# motoko_5_0.net
KiCad netlist of a schematic drawn in EAGLE
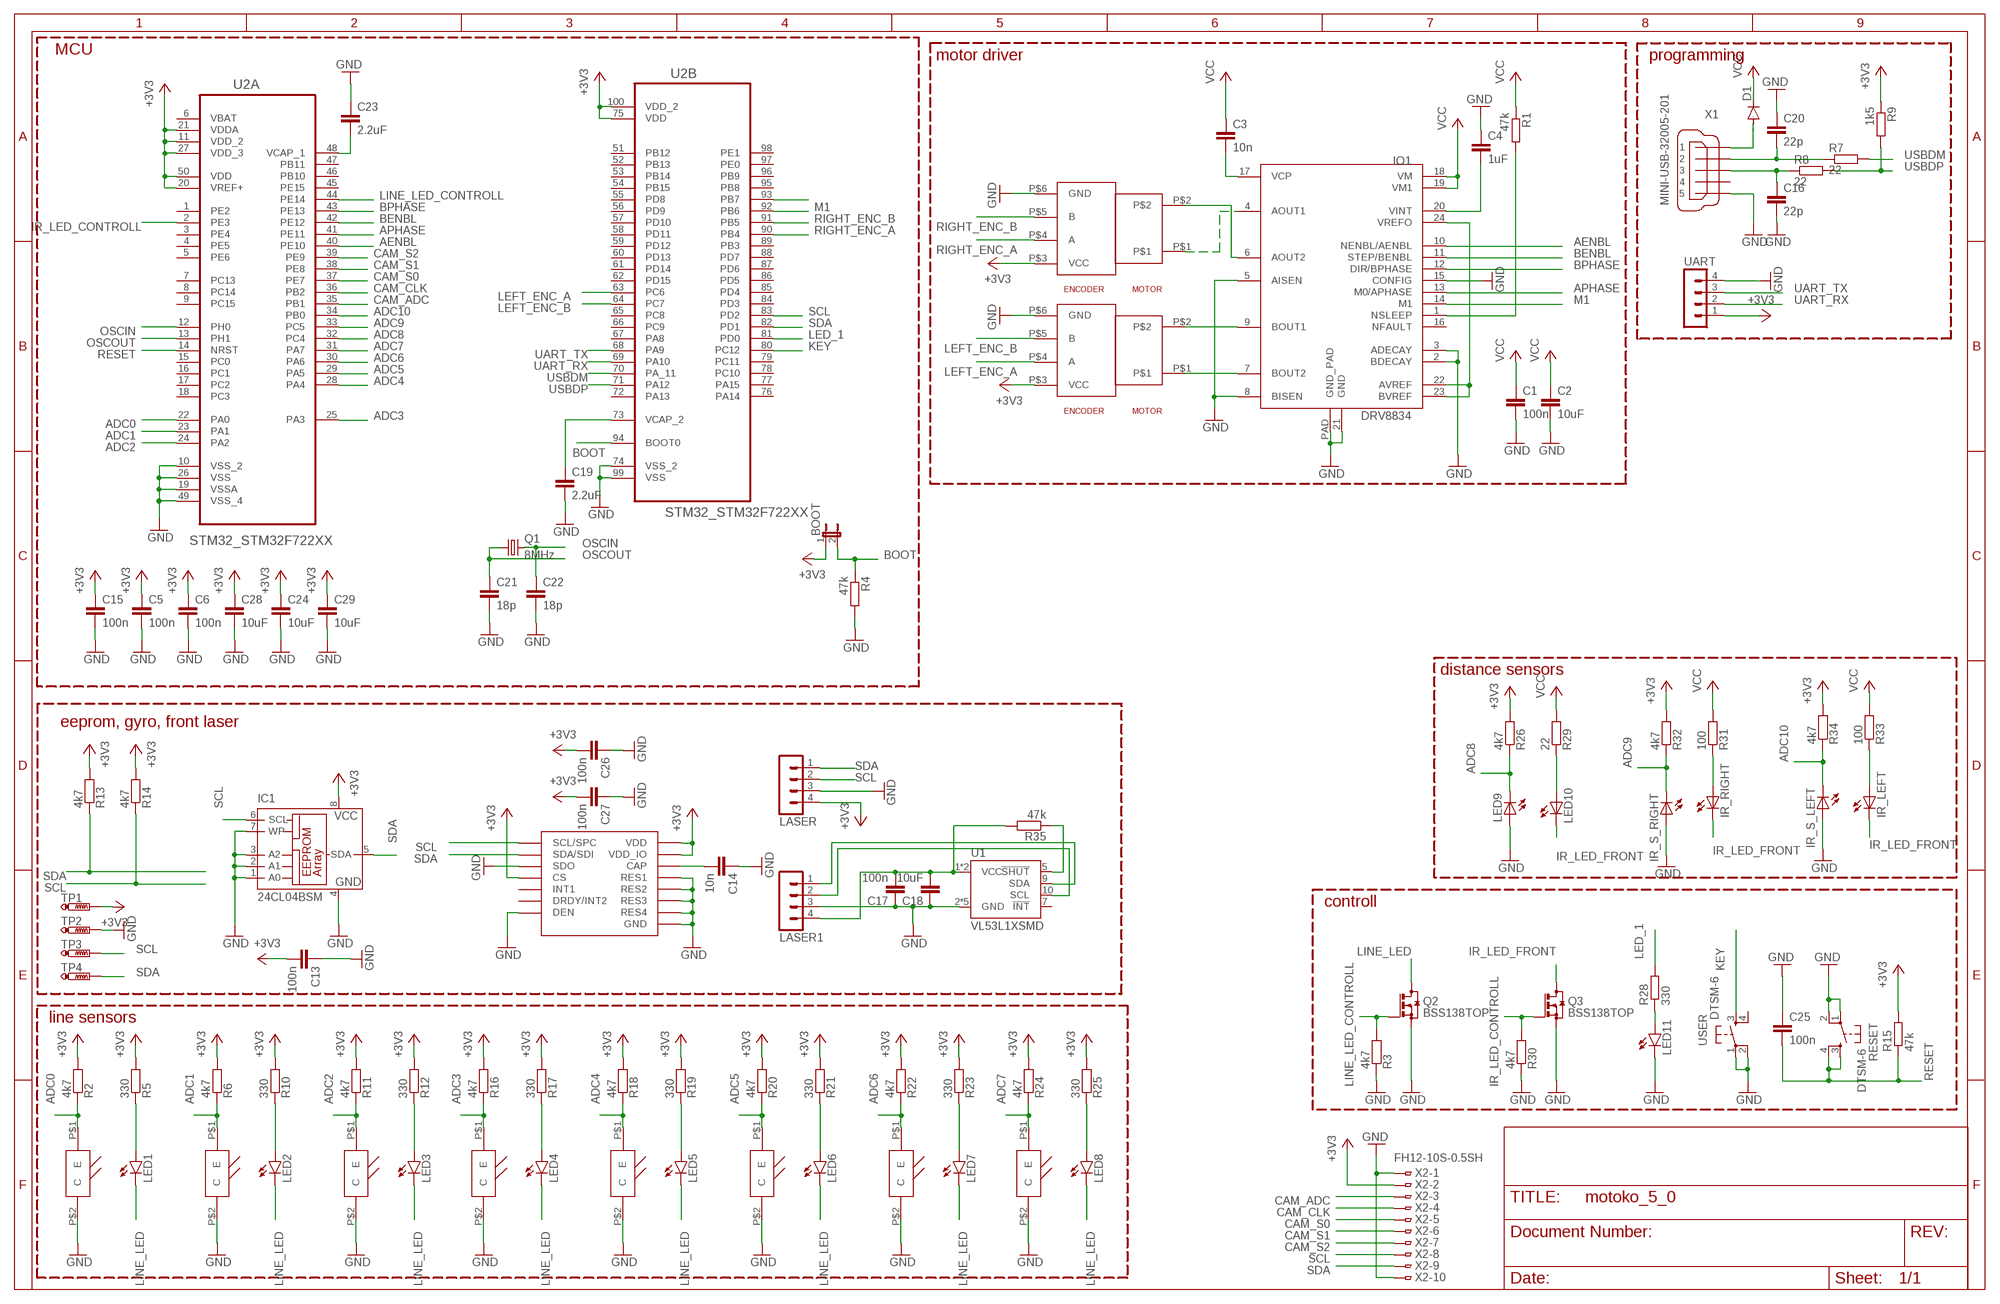
[diagram p0: schematic, sheet 1, part 1 of 2]
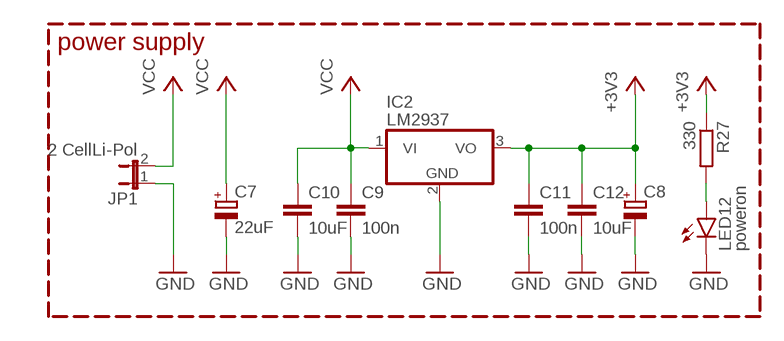
[diagram p1: schematic, sheet 1, part 2 of 2]

(export (version "E")
  (design (tool "Eeschema 10.0.6"))
  (components
    (comp (ref "BOOT")
      (value "JP1E")
      (footprint "eagle-import:JP1")
      (libsource (lib "eagle-import") (part "JP1E"))
    )
    (comp (ref "C1")
      (value "100n")
      (footprint "eagle-import:C1206")
      (libsource (lib "eagle-import") (part "C-EUC1206"))
    )
    (comp (ref "C2")
      (value "10uF")
      (footprint "eagle-import:C1206")
      (libsource (lib "eagle-import") (part "C-EUC1206"))
    )
    (comp (ref "C3")
      (value "10n")
      (footprint "eagle-import:C1206")
      (libsource (lib "eagle-import") (part "C-EUC1206"))
    )
    (comp (ref "C4")
      (value "1uF")
      (footprint "eagle-import:C1206")
      (libsource (lib "eagle-import") (part "C-EUC1206"))
    )
    (comp (ref "C5")
      (value "100n")
      (footprint "eagle-import:C0805")
      (libsource (lib "eagle-import") (part "C-EUC0805"))
    )
    (comp (ref "C6")
      (value "100n")
      (footprint "eagle-import:C0805")
      (libsource (lib "eagle-import") (part "C-EUC0805"))
    )
    (comp (ref "C7")
      (value "22uF")
      (footprint "eagle-import:153CLV-0505")
      (libsource (lib "eagle-import") (part "resistor_348_CPOL-EU153CLV-0505"))
    )
    (comp (ref "C8")
      (value "CPOL-EU140CLH-1010")
      (footprint "eagle-import:140CLH-1010")
      (libsource (lib "eagle-import") (part "CPOL-EU140CLH-1010"))
    )
    (comp (ref "C9")
      (value "100n")
      (footprint "eagle-import:C0805")
      (libsource (lib "eagle-import") (part "C-EUC0805"))
    )
    (comp (ref "C10")
      (value "10uF")
      (footprint "eagle-import:C0805")
      (libsource (lib "eagle-import") (part "C-EUC0805"))
    )
    (comp (ref "C11")
      (value "100n")
      (footprint "eagle-import:C0805")
      (libsource (lib "eagle-import") (part "C-EUC0805"))
    )
    (comp (ref "C12")
      (value "10uF")
      (footprint "eagle-import:C0805")
      (libsource (lib "eagle-import") (part "C-EUC0805"))
    )
    (comp (ref "C13")
      (value "100n")
      (footprint "eagle-import:C0805")
      (libsource (lib "eagle-import") (part "C-EUC0805"))
    )
    (comp (ref "C14")
      (value "10n")
      (footprint "eagle-import:C0805")
      (libsource (lib "eagle-import") (part "C-EUC0805"))
    )
    (comp (ref "C15")
      (value "100n")
      (footprint "eagle-import:C0805")
      (libsource (lib "eagle-import") (part "C-EUC0805"))
    )
    (comp (ref "C16")
      (value "22p")
      (footprint "eagle-import:C0805")
      (libsource (lib "eagle-import") (part "C-EUC0805"))
    )
    (comp (ref "C17")
      (value "100n")
      (footprint "eagle-import:C0805")
      (libsource (lib "eagle-import") (part "C-EUC0805"))
    )
    (comp (ref "C18")
      (value "10uF")
      (footprint "eagle-import:C0805")
      (libsource (lib "eagle-import") (part "C-EUC0805"))
    )
    (comp (ref "C19")
      (value "2.2uF")
      (footprint "eagle-import:C0805")
      (libsource (lib "eagle-import") (part "C-EUC0805"))
    )
    (comp (ref "C20")
      (value "22p")
      (footprint "eagle-import:C0805")
      (libsource (lib "eagle-import") (part "C-EUC0805"))
    )
    (comp (ref "C21")
      (value "18p")
      (footprint "eagle-import:C0805")
      (libsource (lib "eagle-import") (part "C-EUC0805"))
    )
    (comp (ref "C22")
      (value "18p")
      (footprint "eagle-import:C0805")
      (libsource (lib "eagle-import") (part "C-EUC0805"))
    )
    (comp (ref "C23")
      (value "2.2uF")
      (footprint "eagle-import:C0805")
      (libsource (lib "eagle-import") (part "C-EUC0805"))
    )
    (comp (ref "C24")
      (value "10uF")
      (footprint "eagle-import:C0805")
      (libsource (lib "eagle-import") (part "C-EUC0805"))
    )
    (comp (ref "C25")
      (value "100n")
      (footprint "eagle-import:C0805")
      (libsource (lib "eagle-import") (part "C-EUC0805"))
    )
    (comp (ref "C26")
      (value "100n")
      (footprint "eagle-import:C0805")
      (libsource (lib "eagle-import") (part "C-EUC0805"))
    )
    (comp (ref "C27")
      (value "100n")
      (footprint "eagle-import:C0805")
      (libsource (lib "eagle-import") (part "C-EUC0805"))
    )
    (comp (ref "C28")
      (value "10uF")
      (footprint "eagle-import:C0805")
      (libsource (lib "eagle-import") (part "C-EUC0805"))
    )
    (comp (ref "C29")
      (value "10uF")
      (footprint "eagle-import:C0805")
      (libsource (lib "eagle-import") (part "C-EUC0805"))
    )
    (comp (ref "D1")
      (value "DIODE-SMB")
      (footprint "eagle-import:SMB")
      (libsource (lib "eagle-import") (part "DIODE-SMB"))
    )
    (comp (ref "IC1")
      (value "24CL04BSM")
      (footprint "eagle-import:SO-08M")
      (fields (field (name "MPN") "FM24CL04-S"))
      (libsource (lib "eagle-import") (part "24SMCL04B"))
    )
    (comp (ref "IC2")
      (value "LM2937")
      (footprint "eagle-import:TO263-3")
      (libsource (lib "eagle-import") (part "LM2937"))
    )
    (comp (ref "IO1")
      (value "DRV8834")
      (footprint "eagle-import:DRV8834_PCK")
      (libsource (lib "eagle-import") (part "DRV8834"))
    )
    (comp (ref "IR_LEFT")
      (value "LED5MM")
      (footprint "eagle-import:LED5MM")
      (libsource (lib "eagle-import") (part "my_parts_LED5MM"))
    )
    (comp (ref "IR_RIGHT")
      (value "LED5MM")
      (footprint "eagle-import:LED5MM")
      (libsource (lib "eagle-import") (part "my_parts_LED5MM"))
    )
    (comp (ref "IR_S_LEFT")
      (value "LED5MM")
      (footprint "eagle-import:LED5MM")
      (libsource (lib "eagle-import") (part "my_parts_LED5MM"))
    )
    (comp (ref "IR_S_RIGHT")
      (value "LED5MM")
      (footprint "eagle-import:LED5MM")
      (libsource (lib "eagle-import") (part "my_parts_LED5MM"))
    )
    (comp (ref "JP1")
      (value "2 CellLi-Pol")
      (footprint "eagle-import:JP1")
      (libsource (lib "eagle-import") (part "JP1E"))
    )
    (comp (ref "LASER")
      (value "MA04-1")
      (footprint "eagle-import:MA04-1")
      (libsource (lib "eagle-import") (part "MA04-1"))
    )
    (comp (ref "LASER1")
      (value "MA04-1")
      (footprint "eagle-import:MA04-1")
      (libsource (lib "eagle-import") (part "MA04-1"))
    )
    (comp (ref "LED1")
      (value "LEDCHIPLED_1206")
      (footprint "eagle-import:CHIPLED_1206")
      (libsource (lib "eagle-import") (part "LEDCHIPLED_1206"))
    )
    (comp (ref "LED2")
      (value "LEDCHIPLED_1206")
      (footprint "eagle-import:CHIPLED_1206")
      (libsource (lib "eagle-import") (part "LEDCHIPLED_1206"))
    )
    (comp (ref "LED3")
      (value "LEDCHIPLED_1206")
      (footprint "eagle-import:CHIPLED_1206")
      (libsource (lib "eagle-import") (part "LEDCHIPLED_1206"))
    )
    (comp (ref "LED4")
      (value "LEDCHIPLED_1206")
      (footprint "eagle-import:CHIPLED_1206")
      (libsource (lib "eagle-import") (part "LEDCHIPLED_1206"))
    )
    (comp (ref "LED5")
      (value "LEDCHIPLED_1206")
      (footprint "eagle-import:CHIPLED_1206")
      (libsource (lib "eagle-import") (part "LEDCHIPLED_1206"))
    )
    (comp (ref "LED6")
      (value "LEDCHIPLED_1206")
      (footprint "eagle-import:CHIPLED_1206")
      (libsource (lib "eagle-import") (part "LEDCHIPLED_1206"))
    )
    (comp (ref "LED7")
      (value "LEDCHIPLED_1206")
      (footprint "eagle-import:CHIPLED_1206")
      (libsource (lib "eagle-import") (part "LEDCHIPLED_1206"))
    )
    (comp (ref "LED8")
      (value "LEDCHIPLED_1206")
      (footprint "eagle-import:CHIPLED_1206")
      (libsource (lib "eagle-import") (part "LEDCHIPLED_1206"))
    )
    (comp (ref "LED9")
      (value "LED5MM")
      (footprint "eagle-import:LED5MM")
      (libsource (lib "eagle-import") (part "my_parts_LED5MM"))
    )
    (comp (ref "LED10")
      (value "LED5MM")
      (footprint "eagle-import:LED5MM")
      (libsource (lib "eagle-import") (part "my_parts_LED5MM"))
    )
    (comp (ref "LED11")
      (value "LEDCHIPLED_1206")
      (footprint "eagle-import:CHIPLED_1206")
      (libsource (lib "eagle-import") (part "LEDCHIPLED_1206"))
    )
    (comp (ref "LED12")
      (value "poweron")
      (footprint "eagle-import:CHIPLED_1206")
      (libsource (lib "eagle-import") (part "LEDCHIPLED_1206"))
    )
    (comp (ref "LSM6DS0")
      (value "ST_L3GD20H")
      (footprint "eagle-import:ST_LGA16L")
      (libsource (lib "eagle-import") (part "ST_L3GD20H"))
    )
    (comp (ref "Q1")
      (value "8MHz")
      (footprint "eagle-import:CTS406")
      (libsource (lib "eagle-import") (part "CRYSTALCTS406"))
    )
    (comp (ref "Q2")
      (value "BSS138TOP")
      (footprint "eagle-import:SOT23")
      (libsource (lib "eagle-import") (part "BSS138TOP"))
    )
    (comp (ref "Q3")
      (value "BSS138TOP")
      (footprint "eagle-import:SOT23")
      (libsource (lib "eagle-import") (part "BSS138TOP"))
    )
    (comp (ref "R1")
      (value "47k")
      (footprint "eagle-import:M1206")
      (libsource (lib "eagle-import") (part "R-EU_M1206"))
    )
    (comp (ref "R2")
      (value "4k7")
      (footprint "eagle-import:M0805")
      (libsource (lib "eagle-import") (part "R-EU_M0805"))
    )
    (comp (ref "R3")
      (value "4k7")
      (footprint "eagle-import:M0805")
      (libsource (lib "eagle-import") (part "R-EU_M0805"))
    )
    (comp (ref "R4")
      (value "47k")
      (footprint "eagle-import:M0805")
      (libsource (lib "eagle-import") (part "R-EU_M0805"))
    )
    (comp (ref "R5")
      (value "330")
      (footprint "eagle-import:M0805")
      (libsource (lib "eagle-import") (part "R-EU_M0805"))
    )
    (comp (ref "R6")
      (value "4k7")
      (footprint "eagle-import:M0805")
      (libsource (lib "eagle-import") (part "R-EU_M0805"))
    )
    (comp (ref "R7")
      (value "22")
      (footprint "eagle-import:M0805")
      (libsource (lib "eagle-import") (part "R-EU_M0805"))
    )
    (comp (ref "R8")
      (value "22")
      (footprint "eagle-import:M0805")
      (libsource (lib "eagle-import") (part "R-EU_M0805"))
    )
    (comp (ref "R9")
      (value "1k5")
      (footprint "eagle-import:M0805")
      (libsource (lib "eagle-import") (part "R-EU_M0805"))
    )
    (comp (ref "R10")
      (value "330")
      (footprint "eagle-import:M0805")
      (libsource (lib "eagle-import") (part "R-EU_M0805"))
    )
    (comp (ref "R11")
      (value "4k7")
      (footprint "eagle-import:M0805")
      (libsource (lib "eagle-import") (part "R-EU_M0805"))
    )
    (comp (ref "R12")
      (value "330")
      (footprint "eagle-import:M0805")
      (libsource (lib "eagle-import") (part "R-EU_M0805"))
    )
    (comp (ref "R13")
      (value "4k7")
      (footprint "eagle-import:M0805")
      (libsource (lib "eagle-import") (part "R-EU_M0805"))
    )
    (comp (ref "R14")
      (value "4k7")
      (footprint "eagle-import:M0805")
      (libsource (lib "eagle-import") (part "R-EU_M0805"))
    )
    (comp (ref "R15")
      (value "47k")
      (footprint "eagle-import:M0805")
      (libsource (lib "eagle-import") (part "R-EU_M0805"))
    )
    (comp (ref "R16")
      (value "4k7")
      (footprint "eagle-import:M0805")
      (libsource (lib "eagle-import") (part "R-EU_M0805"))
    )
    (comp (ref "R17")
      (value "330")
      (footprint "eagle-import:M0805")
      (libsource (lib "eagle-import") (part "R-EU_M0805"))
    )
    (comp (ref "R18")
      (value "4k7")
      (footprint "eagle-import:M0805")
      (libsource (lib "eagle-import") (part "R-EU_M0805"))
    )
    (comp (ref "R19")
      (value "330")
      (footprint "eagle-import:M0805")
      (libsource (lib "eagle-import") (part "R-EU_M0805"))
    )
    (comp (ref "R20")
      (value "4k7")
      (footprint "eagle-import:M0805")
      (libsource (lib "eagle-import") (part "R-EU_M0805"))
    )
    (comp (ref "R21")
      (value "330")
      (footprint "eagle-import:M0805")
      (libsource (lib "eagle-import") (part "R-EU_M0805"))
    )
    (comp (ref "R22")
      (value "4k7")
      (footprint "eagle-import:M0805")
      (libsource (lib "eagle-import") (part "R-EU_M0805"))
    )
    (comp (ref "R23")
      (value "330")
      (footprint "eagle-import:M0805")
      (libsource (lib "eagle-import") (part "R-EU_M0805"))
    )
    (comp (ref "R24")
      (value "4k7")
      (footprint "eagle-import:M0805")
      (libsource (lib "eagle-import") (part "R-EU_M0805"))
    )
    (comp (ref "R25")
      (value "330")
      (footprint "eagle-import:M0805")
      (libsource (lib "eagle-import") (part "R-EU_M0805"))
    )
    (comp (ref "R26")
      (value "4k7")
      (footprint "eagle-import:M0805")
      (libsource (lib "eagle-import") (part "R-EU_M0805"))
    )
    (comp (ref "R27")
      (value "330")
      (footprint "eagle-import:M0805")
      (libsource (lib "eagle-import") (part "R-EU_M0805"))
    )
    (comp (ref "R28")
      (value "330")
      (footprint "eagle-import:M0805")
      (libsource (lib "eagle-import") (part "R-EU_M0805"))
    )
    (comp (ref "R29")
      (value "22")
      (footprint "eagle-import:M0805")
      (libsource (lib "eagle-import") (part "R-EU_M0805"))
    )
    (comp (ref "R30")
      (value "4k7")
      (footprint "eagle-import:M0805")
      (libsource (lib "eagle-import") (part "R-EU_M0805"))
    )
    (comp (ref "R31")
      (value "100")
      (footprint "eagle-import:M0805")
      (libsource (lib "eagle-import") (part "R-EU_M0805"))
    )
    (comp (ref "R32")
      (value "4k7")
      (footprint "eagle-import:M0805")
      (libsource (lib "eagle-import") (part "R-EU_M0805"))
    )
    (comp (ref "R33")
      (value "100")
      (footprint "eagle-import:M0805")
      (libsource (lib "eagle-import") (part "R-EU_M0805"))
    )
    (comp (ref "R34")
      (value "4k7")
      (footprint "eagle-import:M0805")
      (libsource (lib "eagle-import") (part "R-EU_M0805"))
    )
    (comp (ref "R35")
      (value "47k")
      (footprint "eagle-import:M0805")
      (libsource (lib "eagle-import") (part "R-EU_M0805"))
    )
    (comp (ref "RESET")
      (value "DTSM-6")
      (footprint "eagle-import:DTSM-6")
      (libsource (lib "eagle-import") (part "DTSM-6"))
    )
    (comp (ref "TP1")
      (value "PTR1B1,27")
      (footprint "eagle-import:B1,27")
      (libsource (lib "eagle-import") (part "PTR1B1,27"))
    )
    (comp (ref "TP2")
      (value "PTR1B1,27")
      (footprint "eagle-import:B1,27")
      (libsource (lib "eagle-import") (part "PTR1B1,27"))
    )
    (comp (ref "TP3")
      (value "PTR1B1,27")
      (footprint "eagle-import:B1,27")
      (libsource (lib "eagle-import") (part "PTR1B1,27"))
    )
    (comp (ref "TP4")
      (value "PTR1B1,27")
      (footprint "eagle-import:B1,27")
      (libsource (lib "eagle-import") (part "PTR1B1,27"))
    )
    (comp (ref "U$3")
      (value "SFH3710")
      (footprint "eagle-import:SFH3710")
      (libsource (lib "eagle-import") (part "SFH3710"))
    )
    (comp (ref "U$4")
      (value "SFH3710")
      (footprint "eagle-import:SFH3710")
      (libsource (lib "eagle-import") (part "SFH3710"))
    )
    (comp (ref "U$5")
      (value "SFH3710")
      (footprint "eagle-import:SFH3710")
      (libsource (lib "eagle-import") (part "SFH3710"))
    )
    (comp (ref "U$6")
      (value "SFH3710")
      (footprint "eagle-import:SFH3710")
      (libsource (lib "eagle-import") (part "SFH3710"))
    )
    (comp (ref "U$7")
      (value "SFH3710")
      (footprint "eagle-import:SFH3710")
      (libsource (lib "eagle-import") (part "SFH3710"))
    )
    (comp (ref "U$8")
      (value "SFH3710")
      (footprint "eagle-import:SFH3710")
      (libsource (lib "eagle-import") (part "SFH3710"))
    )
    (comp (ref "U$9")
      (value "SFH3710")
      (footprint "eagle-import:SFH3710")
      (libsource (lib "eagle-import") (part "SFH3710"))
    )
    (comp (ref "U$10")
      (value "SFH3710")
      (footprint "eagle-import:SFH3710")
      (libsource (lib "eagle-import") (part "SFH3710"))
    )
    (comp (ref "U$11")
      (value "POLOLU_GEAR_MOTORPOLO")
      (footprint "eagle-import:POLOLU_GEAR_MOTOR")
      (libsource (lib "eagle-import") (part "POLOLU_GEAR_MOTORPOLO"))
    )
    (comp (ref "U$12")
      (value "POLOLU_GEAR_MOTORPOLO")
      (footprint "eagle-import:POLOLU_GEAR_MOTOR")
      (libsource (lib "eagle-import") (part "POLOLU_GEAR_MOTORPOLO"))
    )
    (comp (ref "U1")
      (value "VL53L1XSMD")
      (footprint "eagle-import:VL53L1X")
      (libsource (lib "eagle-import") (part "VL53L1XSMD"))
    )
    (comp (ref "U2")
      (value "STM32_STM32F722XX")
      (footprint "eagle-import:STM32_QFP50P1600X1600X160-100N")
      (fields (field (name "MPN") "STM32F407VET6"))
      (libsource (lib "eagle-import") (part "STM32_STM32F722XX"))
    )
    (comp (ref "UART")
      (value "MA04-1")
      (footprint "eagle-import:MA04-1")
      (libsource (lib "eagle-import") (part "MA04-1"))
    )
    (comp (ref "USER")
      (value "DTSM-6")
      (footprint "eagle-import:DTSM-6")
      (libsource (lib "eagle-import") (part "DTSM-6"))
    )
    (comp (ref "X1")
      (value "MINI-USB-32005-201")
      (footprint "eagle-import:32005-201")
      (libsource (lib "eagle-import") (part "MINI-USB-32005-201"))
    )
    (comp (ref "X2")
      (value "FH12-10S-0.5SH")
      (footprint "eagle-import:FH12-10S-0.5SH")
      (fields (field (name "MPN") "FH12-10S-0.5SH(55)"))
      (libsource (lib "eagle-import") (part "FH12-10S-0.5SH"))
    )
  )
  (nets
    (net (code "1") (name "+3V3") (class "Default")
      (node (ref "BOOT") (pin "1") (pinfunction "1_1") (pintype "passive"))
      (node (ref "C11") (pin "1") (pinfunction "1_1") (pintype "passive"))
      (node (ref "C12") (pin "1") (pinfunction "1_1") (pintype "passive"))
      (node (ref "C13") (pin "2") (pinfunction "2_2") (pintype "passive"))
      (node (ref "C15") (pin "1") (pinfunction "1_1") (pintype "passive"))
      (node (ref "C24") (pin "1") (pinfunction "1_1") (pintype "passive"))
      (node (ref "C26") (pin "2") (pinfunction "2_2") (pintype "passive"))
      (node (ref "C27") (pin "2") (pinfunction "2_2") (pintype "passive"))
      (node (ref "C28") (pin "1") (pinfunction "1_1") (pintype "passive"))
      (node (ref "C29") (pin "1") (pinfunction "1_1") (pintype "passive"))
      (node (ref "C5") (pin "1") (pinfunction "1_1") (pintype "passive"))
      (node (ref "C6") (pin "1") (pinfunction "1_1") (pintype "passive"))
      (node (ref "C8") (pin "+") (pinfunction "+_+") (pintype "passive"))
      (node (ref "IC1") (pin "8") (pinfunction "VCC_8") (pintype "power_in"))
      (node (ref "IC2") (pin "3") (pinfunction "VO_3") (pintype "passive"))
      (node (ref "LASER") (pin "4") (pinfunction "4_4") (pintype "passive"))
      (node (ref "LSM6DS0") (pin "P$1") (pinfunction "VDD_IO_P$1") (pintype "power_in"))
      (node (ref "LSM6DS0") (pin "P$16") (pinfunction "VDD_P$16") (pintype "power_in"))
      (node (ref "LSM6DS0") (pin "P$5") (pinfunction "CS_P$5") (pintype "bidirectional"))
      (node (ref "R10") (pin "2") (pinfunction "2_2") (pintype "passive"))
      (node (ref "R11") (pin "2") (pinfunction "2_2") (pintype "passive"))
      (node (ref "R12") (pin "2") (pinfunction "2_2") (pintype "passive"))
      (node (ref "R13") (pin "2") (pinfunction "2_2") (pintype "passive"))
      (node (ref "R14") (pin "2") (pinfunction "2_2") (pintype "passive"))
      (node (ref "R15") (pin "2") (pinfunction "2_2") (pintype "passive"))
      (node (ref "R16") (pin "2") (pinfunction "2_2") (pintype "passive"))
      (node (ref "R17") (pin "2") (pinfunction "2_2") (pintype "passive"))
      (node (ref "R18") (pin "2") (pinfunction "2_2") (pintype "passive"))
      (node (ref "R19") (pin "2") (pinfunction "2_2") (pintype "passive"))
      (node (ref "R2") (pin "2") (pinfunction "2_2") (pintype "passive"))
      (node (ref "R20") (pin "2") (pinfunction "2_2") (pintype "passive"))
      (node (ref "R21") (pin "2") (pinfunction "2_2") (pintype "passive"))
      (node (ref "R22") (pin "2") (pinfunction "2_2") (pintype "passive"))
      (node (ref "R23") (pin "2") (pinfunction "2_2") (pintype "passive"))
      (node (ref "R24") (pin "2") (pinfunction "2_2") (pintype "passive"))
      (node (ref "R25") (pin "2") (pinfunction "2_2") (pintype "passive"))
      (node (ref "R26") (pin "2") (pinfunction "2_2") (pintype "passive"))
      (node (ref "R27") (pin "1") (pinfunction "1_1") (pintype "passive"))
      (node (ref "R32") (pin "2") (pinfunction "2_2") (pintype "passive"))
      (node (ref "R34") (pin "2") (pinfunction "2_2") (pintype "passive"))
      (node (ref "R5") (pin "2") (pinfunction "2_2") (pintype "passive"))
      (node (ref "R6") (pin "2") (pinfunction "2_2") (pintype "passive"))
      (node (ref "R9") (pin "1") (pinfunction "1_1") (pintype "passive"))
      (node (ref "TP1") (pin "TP") (pinfunction "TP_TP") (pintype "input"))
      (node (ref "U$11") (pin "P$3") (pinfunction "VCC_P$3") (pintype "bidirectional"))
      (node (ref "U$12") (pin "P$3") (pinfunction "VCC_P$3") (pintype "bidirectional"))
      (node (ref "U2") (pin "100") (pinfunction "VDD_2_100") (pintype "power_in"))
      (node (ref "U2") (pin "11") (pinfunction "VDD_2_11") (pintype "power_in"))
      (node (ref "U2") (pin "20") (pinfunction "VREF+_20") (pintype "power_in"))
      (node (ref "U2") (pin "21") (pinfunction "VDDA_21") (pintype "power_in"))
      (node (ref "U2") (pin "27") (pinfunction "VDD_3_27") (pintype "power_in"))
      (node (ref "U2") (pin "50") (pinfunction "VDD_50") (pintype "power_in"))
      (node (ref "U2") (pin "75") (pinfunction "VDD_75") (pintype "power_in"))
      (node (ref "UART") (pin "1") (pinfunction "1_1") (pintype "passive"))
      (node (ref "X2") (pin "2") (pinfunction "1_2") (pintype "passive"))
    )
    (net (code "2") (name "/ADC0") (class "Default")
      (node (ref "R2") (pin "1") (pinfunction "1_1") (pintype "passive"))
      (node (ref "U$3") (pin "P$1") (pinfunction "E_P$1") (pintype "bidirectional"))
      (node (ref "U2") (pin "22") (pinfunction "PA0_22") (pintype "bidirectional"))
    )
    (net (code "3") (name "/ADC1") (class "Default")
      (node (ref "R6") (pin "1") (pinfunction "1_1") (pintype "passive"))
      (node (ref "U$4") (pin "P$1") (pinfunction "E_P$1") (pintype "bidirectional"))
      (node (ref "U2") (pin "23") (pinfunction "PA1_23") (pintype "bidirectional"))
    )
    (net (code "4") (name "/ADC2") (class "Default")
      (node (ref "R11") (pin "1") (pinfunction "1_1") (pintype "passive"))
      (node (ref "U$5") (pin "P$1") (pinfunction "E_P$1") (pintype "bidirectional"))
      (node (ref "U2") (pin "24") (pinfunction "PA2_24") (pintype "bidirectional"))
    )
    (net (code "5") (name "/ADC3") (class "Default")
      (node (ref "R16") (pin "1") (pinfunction "1_1") (pintype "passive"))
      (node (ref "U$6") (pin "P$1") (pinfunction "E_P$1") (pintype "bidirectional"))
      (node (ref "U2") (pin "25") (pinfunction "PA3_25") (pintype "bidirectional"))
    )
    (net (code "6") (name "/ADC4") (class "Default")
      (node (ref "R18") (pin "1") (pinfunction "1_1") (pintype "passive"))
      (node (ref "U$7") (pin "P$1") (pinfunction "E_P$1") (pintype "bidirectional"))
      (node (ref "U2") (pin "28") (pinfunction "PA4_28") (pintype "bidirectional"))
    )
    (net (code "7") (name "/ADC5") (class "Default")
      (node (ref "R20") (pin "1") (pinfunction "1_1") (pintype "passive"))
      (node (ref "U$8") (pin "P$1") (pinfunction "E_P$1") (pintype "bidirectional"))
      (node (ref "U2") (pin "29") (pinfunction "PA5_29") (pintype "bidirectional"))
    )
    (net (code "8") (name "/ADC6") (class "Default")
      (node (ref "R22") (pin "1") (pinfunction "1_1") (pintype "passive"))
      (node (ref "U$9") (pin "P$1") (pinfunction "E_P$1") (pintype "bidirectional"))
      (node (ref "U2") (pin "30") (pinfunction "PA6_30") (pintype "bidirectional"))
    )
    (net (code "9") (name "/ADC7") (class "Default")
      (node (ref "R24") (pin "1") (pinfunction "1_1") (pintype "passive"))
      (node (ref "U$10") (pin "P$1") (pinfunction "E_P$1") (pintype "bidirectional"))
      (node (ref "U2") (pin "31") (pinfunction "PA7_31") (pintype "bidirectional"))
    )
    (net (code "10") (name "/ADC8") (class "Default")
      (node (ref "LED9") (pin "K") (pinfunction "C_K") (pintype "passive"))
      (node (ref "R26") (pin "1") (pinfunction "1_1") (pintype "passive"))
      (node (ref "U2") (pin "32") (pinfunction "PC4_32") (pintype "bidirectional"))
    )
    (net (code "11") (name "/ADC9") (class "Default")
      (node (ref "IR_S_RIGHT") (pin "K") (pinfunction "C_K") (pintype "passive"))
      (node (ref "R32") (pin "1") (pinfunction "1_1") (pintype "passive"))
      (node (ref "U2") (pin "33") (pinfunction "PC5_33") (pintype "bidirectional"))
    )
    (net (code "12") (name "/ADC10") (class "Default")
      (node (ref "IR_S_LEFT") (pin "K") (pinfunction "C_K") (pintype "passive"))
      (node (ref "R34") (pin "1") (pinfunction "1_1") (pintype "passive"))
      (node (ref "U2") (pin "34") (pinfunction "PB0_34") (pintype "bidirectional"))
    )
    (net (code "13") (name "/AENBL") (class "Default")
      (node (ref "IO1") (pin "10") (pinfunction "NENBL/AENBL_10") (pintype "bidirectional"))
      (node (ref "U2") (pin "40") (pinfunction "PE10_40") (pintype "bidirectional"))
    )
    (net (code "14") (name "/APHASE") (class "Default")
      (node (ref "IO1") (pin "13") (pinfunction "M0/APHASE_13") (pintype "bidirectional"))
      (node (ref "U2") (pin "41") (pinfunction "PE11_41") (pintype "bidirectional"))
    )
    (net (code "15") (name "/BENBL") (class "Default")
      (node (ref "IO1") (pin "11") (pinfunction "STEP/BENBL_11") (pintype "bidirectional"))
      (node (ref "U2") (pin "42") (pinfunction "PE12_42") (pintype "bidirectional"))
    )
    (net (code "16") (name "/BOOT") (class "Default")
      (node (ref "BOOT") (pin "2") (pinfunction "2_2") (pintype "passive"))
      (node (ref "R4") (pin "1") (pinfunction "1_1") (pintype "passive"))
      (node (ref "U2") (pin "94") (pinfunction "BOOT0_94") (pintype "input"))
    )
    (net (code "17") (name "/BPHASE") (class "Default")
      (node (ref "IO1") (pin "12") (pinfunction "DIR/BPHASE_12") (pintype "bidirectional"))
      (node (ref "U2") (pin "43") (pinfunction "PE13_43") (pintype "bidirectional"))
    )
    (net (code "18") (name "/CAM_ADC") (class "Default")
      (node (ref "U2") (pin "35") (pinfunction "PB1_35") (pintype "bidirectional"))
      (node (ref "X2") (pin "3") (pinfunction "1_3") (pintype "passive"))
    )
    (net (code "19") (name "/CAM_CLK") (class "Default")
      (node (ref "U2") (pin "36") (pinfunction "PB2_36") (pintype "bidirectional"))
      (node (ref "X2") (pin "4") (pinfunction "1_4") (pintype "passive"))
    )
    (net (code "20") (name "/CAM_S0") (class "Default")
      (node (ref "U2") (pin "37") (pinfunction "PE7_37") (pintype "bidirectional"))
      (node (ref "X2") (pin "5") (pinfunction "1_5") (pintype "passive"))
    )
    (net (code "21") (name "/CAM_S1") (class "Default")
      (node (ref "U2") (pin "38") (pinfunction "PE8_38") (pintype "bidirectional"))
      (node (ref "X2") (pin "6") (pinfunction "1_6") (pintype "passive"))
    )
    (net (code "22") (name "/CAM_S2") (class "Default")
      (node (ref "U2") (pin "39") (pinfunction "PE9_39") (pintype "bidirectional"))
      (node (ref "X2") (pin "7") (pinfunction "1_7") (pintype "passive"))
    )
    (net (code "23") (name "/IR_LED_CONTROLL") (class "Default")
      (node (ref "Q3") (pin "1") (pinfunction "G_1") (pintype "passive"))
      (node (ref "R30") (pin "2") (pinfunction "2_2") (pintype "passive"))
      (node (ref "U2") (pin "2") (pinfunction "PE3_2") (pintype "bidirectional"))
    )
    (net (code "24") (name "/IR_LED_FRONT") (class "Default")
      (node (ref "IR_LEFT") (pin "K") (pinfunction "C_K") (pintype "passive"))
      (node (ref "IR_RIGHT") (pin "K") (pinfunction "C_K") (pintype "passive"))
      (node (ref "LED10") (pin "K") (pinfunction "C_K") (pintype "passive"))
      (node (ref "Q3") (pin "3") (pinfunction "D_3") (pintype "passive"))
    )
    (net (code "25") (name "/KEY") (class "Default")
      (node (ref "U2") (pin "80") (pinfunction "PC12_80") (pintype "bidirectional"))
      (node (ref "USER") (pin "3") (pinfunction "3_3") (pintype "passive"))
    )
    (net (code "26") (name "/LED_1") (class "Default")
      (node (ref "R28") (pin "2") (pinfunction "2_2") (pintype "passive"))
      (node (ref "U2") (pin "81") (pinfunction "PD0_81") (pintype "bidirectional"))
    )
    (net (code "27") (name "/LEFT_ENC_A") (class "Default")
      (node (ref "U$11") (pin "P$4") (pinfunction "A_P$4") (pintype "bidirectional"))
      (node (ref "U2") (pin "63") (pinfunction "PC6_63") (pintype "bidirectional"))
    )
    (net (code "28") (name "/LEFT_ENC_B") (class "Default")
      (node (ref "U$11") (pin "P$5") (pinfunction "B_P$5") (pintype "bidirectional"))
      (node (ref "U2") (pin "64") (pinfunction "PC7_64") (pintype "bidirectional"))
    )
    (net (code "29") (name "/LINE_LED") (class "Default")
      (node (ref "LED1") (pin "C") (pinfunction "C_C") (pintype "passive"))
      (node (ref "LED2") (pin "C") (pinfunction "C_C") (pintype "passive"))
      (node (ref "LED3") (pin "C") (pinfunction "C_C") (pintype "passive"))
      (node (ref "LED4") (pin "C") (pinfunction "C_C") (pintype "passive"))
      (node (ref "LED5") (pin "C") (pinfunction "C_C") (pintype "passive"))
      (node (ref "LED6") (pin "C") (pinfunction "C_C") (pintype "passive"))
      (node (ref "LED7") (pin "C") (pinfunction "C_C") (pintype "passive"))
      (node (ref "LED8") (pin "C") (pinfunction "C_C") (pintype "passive"))
      (node (ref "Q2") (pin "3") (pinfunction "D_3") (pintype "passive"))
    )
    (net (code "30") (name "/LINE_LED_CONTROLL") (class "Default")
      (node (ref "Q2") (pin "1") (pinfunction "G_1") (pintype "passive"))
      (node (ref "R3") (pin "2") (pinfunction "2_2") (pintype "passive"))
      (node (ref "U2") (pin "44") (pinfunction "PE14_44") (pintype "bidirectional"))
    )
    (net (code "31") (name "/M1") (class "Default")
      (node (ref "IO1") (pin "14") (pinfunction "M1_14") (pintype "bidirectional"))
      (node (ref "U2") (pin "92") (pinfunction "PB6_92") (pintype "bidirectional"))
    )
    (net (code "32") (name "/OSCIN") (class "Default")
      (node (ref "C22") (pin "1") (pinfunction "1_1") (pintype "passive"))
      (node (ref "Q1") (pin "3") (pinfunction "2_3") (pintype "passive"))
      (node (ref "U2") (pin "12") (pinfunction "PH0_12") (pintype "bidirectional"))
    )
    (net (code "33") (name "/OSCOUT") (class "Default")
      (node (ref "C21") (pin "1") (pinfunction "1_1") (pintype "passive"))
      (node (ref "Q1") (pin "1") (pinfunction "1_1") (pintype "passive"))
      (node (ref "U2") (pin "13") (pinfunction "PH1_13") (pintype "bidirectional"))
    )
    (net (code "34") (name "/RESET") (class "Default")
      (node (ref "C25") (pin "2") (pinfunction "2_2") (pintype "passive"))
      (node (ref "R15") (pin "1") (pinfunction "1_1") (pintype "passive"))
      (node (ref "RESET") (pin "3") (pinfunction "3_3") (pintype "passive"))
      (node (ref "RESET") (pin "4") (pinfunction "4_4") (pintype "passive"))
      (node (ref "U2") (pin "14") (pinfunction "NRST_14") (pintype "bidirectional"))
    )
    (net (code "35") (name "/RIGHT_ENC_A") (class "Default")
      (node (ref "U$12") (pin "P$4") (pinfunction "A_P$4") (pintype "bidirectional"))
      (node (ref "U2") (pin "90") (pinfunction "PB4_90") (pintype "bidirectional"))
    )
    (net (code "36") (name "/RIGHT_ENC_B") (class "Default")
      (node (ref "U$12") (pin "P$5") (pinfunction "B_P$5") (pintype "bidirectional"))
      (node (ref "U2") (pin "91") (pinfunction "PB5_91") (pintype "bidirectional"))
    )
    (net (code "37") (name "/SCL") (class "Default")
      (node (ref "IC1") (pin "6") (pinfunction "SCL_6") (pintype "input"))
      (node (ref "LASER") (pin "2") (pinfunction "2_2") (pintype "passive"))
      (node (ref "LSM6DS0") (pin "P$2") (pinfunction "SCL/SPC_P$2") (pintype "bidirectional"))
      (node (ref "R14") (pin "1") (pinfunction "1_1") (pintype "passive"))
      (node (ref "TP3") (pin "TP") (pinfunction "TP_TP") (pintype "input"))
      (node (ref "U2") (pin "83") (pinfunction "PD2_83") (pintype "bidirectional"))
      (node (ref "X2") (pin "8") (pinfunction "1_8") (pintype "passive"))
    )
    (net (code "38") (name "/SDA") (class "Default")
      (node (ref "IC1") (pin "5") (pinfunction "SDA_5") (pintype "bidirectional"))
      (node (ref "LASER") (pin "1") (pinfunction "1_1") (pintype "passive"))
      (node (ref "LSM6DS0") (pin "P$3") (pinfunction "SDA/SDI_P$3") (pintype "bidirectional"))
      (node (ref "R13") (pin "1") (pinfunction "1_1") (pintype "passive"))
      (node (ref "TP4") (pin "TP") (pinfunction "TP_TP") (pintype "input"))
      (node (ref "U2") (pin "82") (pinfunction "PD1_82") (pintype "bidirectional"))
      (node (ref "X2") (pin "9") (pinfunction "1_9") (pintype "passive"))
    )
    (net (code "39") (name "/UART_RX") (class "Default")
      (node (ref "U2") (pin "69") (pinfunction "PA10_69") (pintype "bidirectional"))
      (node (ref "UART") (pin "2") (pinfunction "2_2") (pintype "passive"))
    )
    (net (code "40") (name "/UART_TX") (class "Default")
      (node (ref "U2") (pin "68") (pinfunction "PA9_68") (pintype "bidirectional"))
      (node (ref "UART") (pin "3") (pinfunction "3_3") (pintype "passive"))
    )
    (net (code "41") (name "/USBDM") (class "Default")
      (node (ref "R7") (pin "2") (pinfunction "2_2") (pintype "passive"))
      (node (ref "U2") (pin "70") (pinfunction "PA_11_70") (pintype "bidirectional"))
    )
    (net (code "42") (name "/USBDP") (class "Default")
      (node (ref "R8") (pin "2") (pinfunction "2_2") (pintype "passive"))
      (node (ref "R9") (pin "2") (pinfunction "2_2") (pintype "passive"))
      (node (ref "U2") (pin "71") (pinfunction "PA12_71") (pintype "bidirectional"))
    )
    (net (code "43") (name "/VBAT") (class "Default")
      (node (ref "U2") (pin "6") (pinfunction "VBAT_6") (pintype "power_in"))
    )
    (net (code "44") (name "GND") (class "Default")
      (node (ref "C1") (pin "2") (pinfunction "2_2") (pintype "passive"))
      (node (ref "C10") (pin "2") (pinfunction "2_2") (pintype "passive"))
      (node (ref "C11") (pin "2") (pinfunction "2_2") (pintype "passive"))
      (node (ref "C12") (pin "2") (pinfunction "2_2") (pintype "passive"))
      (node (ref "C13") (pin "1") (pinfunction "1_1") (pintype "passive"))
      (node (ref "C14") (pin "1") (pinfunction "1_1") (pintype "passive"))
      (node (ref "C15") (pin "2") (pinfunction "2_2") (pintype "passive"))
      (node (ref "C16") (pin "2") (pinfunction "2_2") (pintype "passive"))
      (node (ref "C17") (pin "1") (pinfunction "1_1") (pintype "passive"))
      (node (ref "C18") (pin "1") (pinfunction "1_1") (pintype "passive"))
      (node (ref "C19") (pin "2") (pinfunction "2_2") (pintype "passive"))
      (node (ref "C2") (pin "2") (pinfunction "2_2") (pintype "passive"))
      (node (ref "C20") (pin "1") (pinfunction "1_1") (pintype "passive"))
      (node (ref "C21") (pin "2") (pinfunction "2_2") (pintype "passive"))
      (node (ref "C22") (pin "2") (pinfunction "2_2") (pintype "passive"))
      (node (ref "C23") (pin "1") (pinfunction "1_1") (pintype "passive"))
      (node (ref "C24") (pin "2") (pinfunction "2_2") (pintype "passive"))
      (node (ref "C25") (pin "1") (pinfunction "1_1") (pintype "passive"))
      (node (ref "C26") (pin "1") (pinfunction "1_1") (pintype "passive"))
      (node (ref "C27") (pin "1") (pinfunction "1_1") (pintype "passive"))
      (node (ref "C28") (pin "2") (pinfunction "2_2") (pintype "passive"))
      (node (ref "C29") (pin "2") (pinfunction "2_2") (pintype "passive"))
      (node (ref "C4") (pin "1") (pinfunction "1_1") (pintype "passive"))
      (node (ref "C5") (pin "2") (pinfunction "2_2") (pintype "passive"))
      (node (ref "C6") (pin "2") (pinfunction "2_2") (pintype "passive"))
      (node (ref "C7") (pin "-") (pinfunction "-_-") (pintype "passive"))
      (node (ref "C8") (pin "-") (pinfunction "-_-") (pintype "passive"))
      (node (ref "C9") (pin "2") (pinfunction "2_2") (pintype "passive"))
      (node (ref "IC1") (pin "1") (pinfunction "A0_1") (pintype "input"))
      (node (ref "IC1") (pin "2") (pinfunction "A1_2") (pintype "input"))
      (node (ref "IC1") (pin "3") (pinfunction "A2_3") (pintype "input"))
      (node (ref "IC1") (pin "4") (pinfunction "GND_4") (pintype "power_in"))
      (node (ref "IC1") (pin "7") (pinfunction "WP_7") (pintype "input"))
      (node (ref "IC2") (pin "2") (pinfunction "GND_2") (pintype "passive"))
      (node (ref "IO1") (pin "15") (pinfunction "CONFIG_15") (pintype "bidirectional"))
      (node (ref "IO1") (pin "2") (pinfunction "BDECAY_2") (pintype "bidirectional"))
      (node (ref "IO1") (pin "21") (pinfunction "GND_21") (pintype "bidirectional"))
      (node (ref "IO1") (pin "3") (pinfunction "ADECAY_3") (pintype "bidirectional"))
      (node (ref "IO1") (pin "5") (pinfunction "AISEN_5") (pintype "bidirectional"))
      (node (ref "IO1") (pin "8") (pinfunction "BISEN_8") (pintype "bidirectional"))
      (node (ref "IO1") (pin "PAD") (pinfunction "GND_PAD_PAD") (pintype "bidirectional"))
      (node (ref "IR_S_LEFT") (pin "A") (pinfunction "A_A") (pintype "passive"))
      (node (ref "IR_S_RIGHT") (pin "A") (pinfunction "A_A") (pintype "passive"))
      (node (ref "JP1") (pin "1") (pinfunction "1_1") (pintype "passive"))
      (node (ref "LASER") (pin "3") (pinfunction "3_3") (pintype "passive"))
      (node (ref "LASER1") (pin "3") (pinfunction "3_3") (pintype "passive"))
      (node (ref "LED11") (pin "C") (pinfunction "C_C") (pintype "passive"))
      (node (ref "LED12") (pin "C") (pinfunction "C_C") (pintype "passive"))
      (node (ref "LED9") (pin "A") (pinfunction "A_A") (pintype "passive"))
      (node (ref "LSM6DS0") (pin "P$10") (pinfunction "RES2_P$10") (pintype "bidirectional"))
      (node (ref "LSM6DS0") (pin "P$11") (pinfunction "RES3_P$11") (pintype "bidirectional"))
      (node (ref "LSM6DS0") (pin "P$12") (pinfunction "GND_P$12") (pintype "power_in"))
      (node (ref "LSM6DS0") (pin "P$13") (pinfunction "GND_P$13") (pintype "power_in"))
      (node (ref "LSM6DS0") (pin "P$15") (pinfunction "RES4_P$15") (pintype "bidirectional"))
      (node (ref "LSM6DS0") (pin "P$4") (pinfunction "SDO_P$4") (pintype "bidirectional"))
      (node (ref "LSM6DS0") (pin "P$8") (pinfunction "DEN_P$8") (pintype "bidirectional"))
      (node (ref "LSM6DS0") (pin "P$9") (pinfunction "RES1_P$9") (pintype "bidirectional"))
      (node (ref "Q2") (pin "2") (pinfunction "S_2") (pintype "passive"))
      (node (ref "Q3") (pin "2") (pinfunction "S_2") (pintype "passive"))
      (node (ref "R3") (pin "1") (pinfunction "1_1") (pintype "passive"))
      (node (ref "R30") (pin "1") (pinfunction "1_1") (pintype "passive"))
      (node (ref "R4") (pin "2") (pinfunction "2_2") (pintype "passive"))
      (node (ref "RESET") (pin "1") (pinfunction "1_1") (pintype "passive"))
      (node (ref "RESET") (pin "2") (pinfunction "2_2") (pintype "passive"))
      (node (ref "TP2") (pin "TP") (pinfunction "TP_TP") (pintype "input"))
      (node (ref "U$10") (pin "P$2") (pinfunction "C_P$2") (pintype "bidirectional"))
      (node (ref "U$11") (pin "P$6") (pinfunction "GND_P$6") (pintype "bidirectional"))
      (node (ref "U$12") (pin "P$6") (pinfunction "GND_P$6") (pintype "bidirectional"))
      (node (ref "U$3") (pin "P$2") (pinfunction "C_P$2") (pintype "bidirectional"))
      (node (ref "U$4") (pin "P$2") (pinfunction "C_P$2") (pintype "bidirectional"))
      (node (ref "U$5") (pin "P$2") (pinfunction "C_P$2") (pintype "bidirectional"))
      (node (ref "U$6") (pin "P$2") (pinfunction "C_P$2") (pintype "bidirectional"))
      (node (ref "U$7") (pin "P$2") (pinfunction "C_P$2") (pintype "bidirectional"))
      (node (ref "U$8") (pin "P$2") (pinfunction "C_P$2") (pintype "bidirectional"))
      (node (ref "U$9") (pin "P$2") (pinfunction "C_P$2") (pintype "bidirectional"))
      (node (ref "U1") (pin "12") (pinfunction "GND_12") (pintype "bidirectional"))
      (node (ref "U1") (pin "2") (pinfunction "GND_2") (pintype "bidirectional"))
      (node (ref "U1") (pin "3") (pinfunction "GND_3") (pintype "bidirectional"))
      (node (ref "U1") (pin "4") (pinfunction "GND_4") (pintype "bidirectional"))
      (node (ref "U1") (pin "6") (pinfunction "GND_6") (pintype "bidirectional"))
      (node (ref "U2") (pin "10") (pinfunction "VSS_2_10") (pintype "passive"))
      (node (ref "U2") (pin "19") (pinfunction "VSSA_19") (pintype "passive"))
      (node (ref "U2") (pin "26") (pinfunction "VSS_26") (pintype "passive"))
      (node (ref "U2") (pin "49") (pinfunction "VSS_4_49") (pintype "power_in"))
      (node (ref "U2") (pin "74") (pinfunction "VSS_2_74") (pintype "passive"))
      (node (ref "U2") (pin "99") (pinfunction "VSS_99") (pintype "passive"))
      (node (ref "UART") (pin "4") (pinfunction "4_4") (pintype "passive"))
      (node (ref "USER") (pin "1") (pinfunction "1_1") (pintype "passive"))
      (node (ref "USER") (pin "2") (pinfunction "2_2") (pintype "passive"))
      (node (ref "X1") (pin "5") (pinfunction "5_5") (pintype "passive"))
      (node (ref "X2") (pin "1") (pinfunction "1_1") (pintype "passive"))
      (node (ref "X2") (pin "10") (pinfunction "1_10") (pintype "passive"))
    )
    (net (code "45") (name "Net-(C16-Pad1)") (class "Default")
      (node (ref "C16") (pin "1") (pinfunction "1_1") (pintype "passive"))
      (node (ref "R8") (pin "1") (pinfunction "1_1") (pintype "passive"))
      (node (ref "X1") (pin "3") (pinfunction "3_3") (pintype "passive"))
    )
    (net (code "46") (name "Net-(C17-Pad2)") (class "Default")
      (node (ref "C17") (pin "2") (pinfunction "2_2") (pintype "passive"))
      (node (ref "C18") (pin "2") (pinfunction "2_2") (pintype "passive"))
      (node (ref "LASER1") (pin "4") (pinfunction "4_4") (pintype "passive"))
      (node (ref "R35") (pin "2") (pinfunction "2_2") (pintype "passive"))
      (node (ref "U1") (pin "1") (pinfunction "VCC_1") (pintype "bidirectional"))
      (node (ref "U1") (pin "11") (pinfunction "VCC_11") (pintype "bidirectional"))
    )
    (net (code "47") (name "Net-(C20-Pad2)") (class "Default")
      (node (ref "C20") (pin "2") (pinfunction "2_2") (pintype "passive"))
      (node (ref "R7") (pin "1") (pinfunction "1_1") (pintype "passive"))
      (node (ref "X1") (pin "2") (pinfunction "2_2") (pintype "passive"))
    )
    (net (code "48") (name "Net-(D1-PadA)") (class "Default")
      (node (ref "D1") (pin "A") (pinfunction "A_A") (pintype "passive"))
      (node (ref "X1") (pin "1") (pinfunction "1_1") (pintype "passive"))
    )
    (net (code "49") (name "Net-(IO1-AOUT1)") (class "Default")
      (node (ref "IO1") (pin "4") (pinfunction "AOUT1_4") (pintype "bidirectional"))
      (node (ref "U$12") (pin "P$1") (pinfunction "P$1_P$1") (pintype "bidirectional"))
    )
    (net (code "50") (name "Net-(IO1-AOUT2)") (class "Default")
      (node (ref "IO1") (pin "6") (pinfunction "AOUT2_6") (pintype "bidirectional"))
      (node (ref "U$12") (pin "P$2") (pinfunction "P$2_P$2") (pintype "bidirectional"))
    )
    (net (code "51") (name "Net-(IO1-AVREF)") (class "Default")
      (node (ref "IO1") (pin "22") (pinfunction "AVREF_22") (pintype "bidirectional"))
      (node (ref "IO1") (pin "23") (pinfunction "BVREF_23") (pintype "bidirectional"))
      (node (ref "IO1") (pin "24") (pinfunction "VREFO_24") (pintype "bidirectional"))
    )
    (net (code "52") (name "Net-(IO1-BOUT1)") (class "Default")
      (node (ref "IO1") (pin "9") (pinfunction "BOUT1_9") (pintype "bidirectional"))
      (node (ref "U$11") (pin "P$2") (pinfunction "P$2_P$2") (pintype "bidirectional"))
    )
    (net (code "53") (name "Net-(IO1-BOUT2)") (class "Default")
      (node (ref "IO1") (pin "7") (pinfunction "BOUT2_7") (pintype "bidirectional"))
      (node (ref "U$11") (pin "P$1") (pinfunction "P$1_P$1") (pintype "bidirectional"))
    )
    (net (code "54") (name "Net-(IO1-NSLEEP)") (class "Default")
      (node (ref "IO1") (pin "1") (pinfunction "NSLEEP_1") (pintype "bidirectional"))
      (node (ref "R1") (pin "2") (pinfunction "2_2") (pintype "passive"))
    )
    (net (code "55") (name "Net-(IO1-VCP)") (class "Default")
      (node (ref "C3") (pin "2") (pinfunction "2_2") (pintype "passive"))
      (node (ref "IO1") (pin "17") (pinfunction "VCP_17") (pintype "bidirectional"))
    )
    (net (code "56") (name "Net-(IO1-VINT)") (class "Default")
      (node (ref "C4") (pin "2") (pinfunction "2_2") (pintype "passive"))
      (node (ref "IO1") (pin "20") (pinfunction "VINT_20") (pintype "bidirectional"))
    )
    (net (code "57") (name "Net-(IR_LEFT-PadA)") (class "Default")
      (node (ref "IR_LEFT") (pin "A") (pinfunction "A_A") (pintype "passive"))
      (node (ref "R33") (pin "1") (pinfunction "1_1") (pintype "passive"))
    )
    (net (code "58") (name "Net-(IR_RIGHT-PadA)") (class "Default")
      (node (ref "IR_RIGHT") (pin "A") (pinfunction "A_A") (pintype "passive"))
      (node (ref "R31") (pin "1") (pinfunction "1_1") (pintype "passive"))
    )
    (net (code "59") (name "Net-(LED1-PadA)") (class "Default")
      (node (ref "LED1") (pin "A") (pinfunction "A_A") (pintype "passive"))
      (node (ref "R5") (pin "1") (pinfunction "1_1") (pintype "passive"))
    )
    (net (code "60") (name "Net-(LED2-PadA)") (class "Default")
      (node (ref "LED2") (pin "A") (pinfunction "A_A") (pintype "passive"))
      (node (ref "R10") (pin "1") (pinfunction "1_1") (pintype "passive"))
    )
    (net (code "61") (name "Net-(LED3-PadA)") (class "Default")
      (node (ref "LED3") (pin "A") (pinfunction "A_A") (pintype "passive"))
      (node (ref "R12") (pin "1") (pinfunction "1_1") (pintype "passive"))
    )
    (net (code "62") (name "Net-(LED4-PadA)") (class "Default")
      (node (ref "LED4") (pin "A") (pinfunction "A_A") (pintype "passive"))
      (node (ref "R17") (pin "1") (pinfunction "1_1") (pintype "passive"))
    )
    (net (code "63") (name "Net-(LED5-PadA)") (class "Default")
      (node (ref "LED5") (pin "A") (pinfunction "A_A") (pintype "passive"))
      (node (ref "R19") (pin "1") (pinfunction "1_1") (pintype "passive"))
    )
    (net (code "64") (name "Net-(LED6-PadA)") (class "Default")
      (node (ref "LED6") (pin "A") (pinfunction "A_A") (pintype "passive"))
      (node (ref "R21") (pin "1") (pinfunction "1_1") (pintype "passive"))
    )
    (net (code "65") (name "Net-(LED7-PadA)") (class "Default")
      (node (ref "LED7") (pin "A") (pinfunction "A_A") (pintype "passive"))
      (node (ref "R23") (pin "1") (pinfunction "1_1") (pintype "passive"))
    )
    (net (code "66") (name "Net-(LED8-PadA)") (class "Default")
      (node (ref "LED8") (pin "A") (pinfunction "A_A") (pintype "passive"))
      (node (ref "R25") (pin "1") (pinfunction "1_1") (pintype "passive"))
    )
    (net (code "67") (name "Net-(LED10-PadA)") (class "Default")
      (node (ref "LED10") (pin "A") (pinfunction "A_A") (pintype "passive"))
      (node (ref "R29") (pin "1") (pinfunction "1_1") (pintype "passive"))
    )
    (net (code "68") (name "Net-(LED11-PadA)") (class "Default")
      (node (ref "LED11") (pin "A") (pinfunction "A_A") (pintype "passive"))
      (node (ref "R28") (pin "1") (pinfunction "1_1") (pintype "passive"))
    )
    (net (code "69") (name "Net-(LED12-PadA)") (class "Default")
      (node (ref "LED12") (pin "A") (pinfunction "A_A") (pintype "passive"))
      (node (ref "R27") (pin "2") (pinfunction "2_2") (pintype "passive"))
    )
    (net (code "70") (name "Net-(LSM6DS0-CAP)") (class "Default")
      (node (ref "C14") (pin "2") (pinfunction "2_2") (pintype "passive"))
      (node (ref "LSM6DS0") (pin "P$14") (pinfunction "CAP_P$14") (pintype "bidirectional"))
    )
    (net (code "71") (name "Net-(U1-SCL)") (class "Default")
      (node (ref "LASER1") (pin "2") (pinfunction "2_2") (pintype "passive"))
      (node (ref "U1") (pin "10") (pinfunction "SCL_10") (pintype "bidirectional"))
    )
    (net (code "72") (name "Net-(U1-SDA)") (class "Default")
      (node (ref "LASER1") (pin "1") (pinfunction "1_1") (pintype "passive"))
      (node (ref "U1") (pin "9") (pinfunction "SDA_9") (pintype "bidirectional"))
    )
    (net (code "73") (name "Net-(U1-~{SHUT})") (class "Default")
      (node (ref "R35") (pin "1") (pinfunction "1_1") (pintype "passive"))
      (node (ref "U1") (pin "5") (pinfunction "~{SHUT}_5") (pintype "bidirectional"))
    )
    (net (code "74") (name "Net-(U2A-VCAP_1)") (class "Default")
      (node (ref "C23") (pin "2") (pinfunction "2_2") (pintype "passive"))
      (node (ref "U2") (pin "48") (pinfunction "VCAP_1_48") (pintype "power_in"))
    )
    (net (code "75") (name "Net-(U2B-VCAP_2)") (class "Default")
      (node (ref "C19") (pin "1") (pinfunction "1_1") (pintype "passive"))
      (node (ref "U2") (pin "73") (pinfunction "VCAP_2_73") (pintype "power_in"))
    )
    (net (code "76") (name "VCC") (class "Default")
      (node (ref "C1") (pin "1") (pinfunction "1_1") (pintype "passive"))
      (node (ref "C10") (pin "1") (pinfunction "1_1") (pintype "passive"))
      (node (ref "C2") (pin "1") (pinfunction "1_1") (pintype "passive"))
      (node (ref "C3") (pin "1") (pinfunction "1_1") (pintype "passive"))
      (node (ref "C7") (pin "+") (pinfunction "+_+") (pintype "passive"))
      (node (ref "C9") (pin "1") (pinfunction "1_1") (pintype "passive"))
      (node (ref "D1") (pin "C") (pinfunction "C_C") (pintype "passive"))
      (node (ref "IC2") (pin "1") (pinfunction "VI_1") (pintype "input"))
      (node (ref "IO1") (pin "18") (pinfunction "VM_18") (pintype "bidirectional"))
      (node (ref "IO1") (pin "19") (pinfunction "VM1_19") (pintype "bidirectional"))
      (node (ref "JP1") (pin "2") (pinfunction "2_2") (pintype "passive"))
      (node (ref "R1") (pin "1") (pinfunction "1_1") (pintype "passive"))
      (node (ref "R29") (pin "2") (pinfunction "2_2") (pintype "passive"))
      (node (ref "R31") (pin "2") (pinfunction "2_2") (pintype "passive"))
      (node (ref "R33") (pin "2") (pinfunction "2_2") (pintype "passive"))
    )
    (net (code "77") (name "unconnected-(IO1-NFAULT-Pad16)") (class "Default")
      (node (ref "IO1") (pin "16") (pinfunction "NFAULT_16") (pintype "bidirectional"))
    )
    (net (code "78") (name "unconnected-(LSM6DS0-DRDY{slash}INT2-PadP$6)") (class "Default")
      (node (ref "LSM6DS0") (pin "P$6") (pinfunction "DRDY/INT2_P$6") (pintype "bidirectional"))
    )
    (net (code "79") (name "unconnected-(LSM6DS0-INT1-PadP$7)") (class "Default")
      (node (ref "LSM6DS0") (pin "P$7") (pinfunction "INT1_P$7") (pintype "bidirectional"))
    )
    (net (code "80") (name "unconnected-(U1-~{INT}-Pad7)") (class "Default")
      (node (ref "U1") (pin "7") (pinfunction "~{INT}_7") (pintype "bidirectional"))
    )
    (net (code "81") (name "unconnected-(U2A-PB10-Pad46)") (class "Default")
      (node (ref "U2") (pin "46") (pinfunction "PB10_46") (pintype "bidirectional"))
    )
    (net (code "82") (name "unconnected-(U2A-PB11-Pad47)") (class "Default")
      (node (ref "U2") (pin "47") (pinfunction "PB11_47") (pintype "bidirectional"))
    )
    (net (code "83") (name "unconnected-(U2A-PC0-Pad15)") (class "Default")
      (node (ref "U2") (pin "15") (pinfunction "PC0_15") (pintype "bidirectional"))
    )
    (net (code "84") (name "unconnected-(U2A-PC1-Pad16)") (class "Default")
      (node (ref "U2") (pin "16") (pinfunction "PC1_16") (pintype "bidirectional"))
    )
    (net (code "85") (name "unconnected-(U2A-PC2-Pad17)") (class "Default")
      (node (ref "U2") (pin "17") (pinfunction "PC2_17") (pintype "bidirectional"))
    )
    (net (code "86") (name "unconnected-(U2A-PC3-Pad18)") (class "Default")
      (node (ref "U2") (pin "18") (pinfunction "PC3_18") (pintype "bidirectional"))
    )
    (net (code "87") (name "unconnected-(U2A-PC13-Pad7)") (class "Default")
      (node (ref "U2") (pin "7") (pinfunction "PC13_7") (pintype "bidirectional"))
    )
    (net (code "88") (name "unconnected-(U2A-PC14-Pad8)") (class "Default")
      (node (ref "U2") (pin "8") (pinfunction "PC14_8") (pintype "bidirectional"))
    )
    (net (code "89") (name "unconnected-(U2A-PC15-Pad9)") (class "Default")
      (node (ref "U2") (pin "9") (pinfunction "PC15_9") (pintype "bidirectional"))
    )
    (net (code "90") (name "unconnected-(U2A-PE2-Pad1)") (class "Default")
      (node (ref "U2") (pin "1") (pinfunction "PE2_1") (pintype "bidirectional"))
    )
    (net (code "91") (name "unconnected-(U2A-PE4-Pad3)") (class "Default")
      (node (ref "U2") (pin "3") (pinfunction "PE4_3") (pintype "bidirectional"))
    )
    (net (code "92") (name "unconnected-(U2A-PE5-Pad4)") (class "Default")
      (node (ref "U2") (pin "4") (pinfunction "PE5_4") (pintype "bidirectional"))
    )
    (net (code "93") (name "unconnected-(U2A-PE6-Pad5)") (class "Default")
      (node (ref "U2") (pin "5") (pinfunction "PE6_5") (pintype "bidirectional"))
    )
    (net (code "94") (name "unconnected-(U2A-PE15-Pad45)") (class "Default")
      (node (ref "U2") (pin "45") (pinfunction "PE15_45") (pintype "bidirectional"))
    )
    (net (code "95") (name "unconnected-(U2B-PA8-Pad67)") (class "Default")
      (node (ref "U2") (pin "67") (pinfunction "PA8_67") (pintype "bidirectional"))
    )
    (net (code "96") (name "unconnected-(U2B-PA13-Pad72)") (class "Default")
      (node (ref "U2") (pin "72") (pinfunction "PA13_72") (pintype "bidirectional"))
    )
    (net (code "97") (name "unconnected-(U2B-PA14-Pad76)") (class "Default")
      (node (ref "U2") (pin "76") (pinfunction "PA14_76") (pintype "bidirectional"))
    )
    (net (code "98") (name "unconnected-(U2B-PA15-Pad77)") (class "Default")
      (node (ref "U2") (pin "77") (pinfunction "PA15_77") (pintype "bidirectional"))
    )
    (net (code "99") (name "unconnected-(U2B-PB3-Pad89)") (class "Default")
      (node (ref "U2") (pin "89") (pinfunction "PB3_89") (pintype "bidirectional"))
    )
    (net (code "100") (name "unconnected-(U2B-PB7-Pad93)") (class "Default")
      (node (ref "U2") (pin "93") (pinfunction "PB7_93") (pintype "bidirectional"))
    )
    (net (code "101") (name "unconnected-(U2B-PB8-Pad95)") (class "Default")
      (node (ref "U2") (pin "95") (pinfunction "PB8_95") (pintype "bidirectional"))
    )
    (net (code "102") (name "unconnected-(U2B-PB9-Pad96)") (class "Default")
      (node (ref "U2") (pin "96") (pinfunction "PB9_96") (pintype "bidirectional"))
    )
    (net (code "103") (name "unconnected-(U2B-PB12-Pad51)") (class "Default")
      (node (ref "U2") (pin "51") (pinfunction "PB12_51") (pintype "bidirectional"))
    )
    (net (code "104") (name "unconnected-(U2B-PB13-Pad52)") (class "Default")
      (node (ref "U2") (pin "52") (pinfunction "PB13_52") (pintype "bidirectional"))
    )
    (net (code "105") (name "unconnected-(U2B-PB14-Pad53)") (class "Default")
      (node (ref "U2") (pin "53") (pinfunction "PB14_53") (pintype "bidirectional"))
    )
    (net (code "106") (name "unconnected-(U2B-PB15-Pad54)") (class "Default")
      (node (ref "U2") (pin "54") (pinfunction "PB15_54") (pintype "bidirectional"))
    )
    (net (code "107") (name "unconnected-(U2B-PC8-Pad65)") (class "Default")
      (node (ref "U2") (pin "65") (pinfunction "PC8_65") (pintype "bidirectional"))
    )
    (net (code "108") (name "unconnected-(U2B-PC9-Pad66)") (class "Default")
      (node (ref "U2") (pin "66") (pinfunction "PC9_66") (pintype "bidirectional"))
    )
    (net (code "109") (name "unconnected-(U2B-PC10-Pad78)") (class "Default")
      (node (ref "U2") (pin "78") (pinfunction "PC10_78") (pintype "bidirectional"))
    )
    (net (code "110") (name "unconnected-(U2B-PC11-Pad79)") (class "Default")
      (node (ref "U2") (pin "79") (pinfunction "PC11_79") (pintype "bidirectional"))
    )
    (net (code "111") (name "unconnected-(U2B-PD3-Pad84)") (class "Default")
      (node (ref "U2") (pin "84") (pinfunction "PD3_84") (pintype "bidirectional"))
    )
    (net (code "112") (name "unconnected-(U2B-PD4-Pad85)") (class "Default")
      (node (ref "U2") (pin "85") (pinfunction "PD4_85") (pintype "bidirectional"))
    )
    (net (code "113") (name "unconnected-(U2B-PD5-Pad86)") (class "Default")
      (node (ref "U2") (pin "86") (pinfunction "PD5_86") (pintype "bidirectional"))
    )
    (net (code "114") (name "unconnected-(U2B-PD6-Pad87)") (class "Default")
      (node (ref "U2") (pin "87") (pinfunction "PD6_87") (pintype "bidirectional"))
    )
    (net (code "115") (name "unconnected-(U2B-PD7-Pad88)") (class "Default")
      (node (ref "U2") (pin "88") (pinfunction "PD7_88") (pintype "bidirectional"))
    )
    (net (code "116") (name "unconnected-(U2B-PD8-Pad55)") (class "Default")
      (node (ref "U2") (pin "55") (pinfunction "PD8_55") (pintype "bidirectional"))
    )
    (net (code "117") (name "unconnected-(U2B-PD9-Pad56)") (class "Default")
      (node (ref "U2") (pin "56") (pinfunction "PD9_56") (pintype "bidirectional"))
    )
    (net (code "118") (name "unconnected-(U2B-PD10-Pad57)") (class "Default")
      (node (ref "U2") (pin "57") (pinfunction "PD10_57") (pintype "bidirectional"))
    )
    (net (code "119") (name "unconnected-(U2B-PD11-Pad58)") (class "Default")
      (node (ref "U2") (pin "58") (pinfunction "PD11_58") (pintype "bidirectional"))
    )
    (net (code "120") (name "unconnected-(U2B-PD12-Pad59)") (class "Default")
      (node (ref "U2") (pin "59") (pinfunction "PD12_59") (pintype "bidirectional"))
    )
    (net (code "121") (name "unconnected-(U2B-PD13-Pad60)") (class "Default")
      (node (ref "U2") (pin "60") (pinfunction "PD13_60") (pintype "bidirectional"))
    )
    (net (code "122") (name "unconnected-(U2B-PD14-Pad61)") (class "Default")
      (node (ref "U2") (pin "61") (pinfunction "PD14_61") (pintype "bidirectional"))
    )
    (net (code "123") (name "unconnected-(U2B-PD15-Pad62)") (class "Default")
      (node (ref "U2") (pin "62") (pinfunction "PD15_62") (pintype "bidirectional"))
    )
    (net (code "124") (name "unconnected-(U2B-PE0-Pad97)") (class "Default")
      (node (ref "U2") (pin "97") (pinfunction "PE0_97") (pintype "bidirectional"))
    )
    (net (code "125") (name "unconnected-(U2B-PE1-Pad98)") (class "Default")
      (node (ref "U2") (pin "98") (pinfunction "PE1_98") (pintype "bidirectional"))
    )
    (net (code "126") (name "unconnected-(USER-Pad4)") (class "Default")
      (node (ref "USER") (pin "4") (pinfunction "4_4") (pintype "passive"))
    )
    (net (code "127") (name "unconnected-(X1-Pad4)") (class "Default")
      (node (ref "X1") (pin "4") (pinfunction "4_4") (pintype "passive"))
    )
  )
)
